# VDMEDA_DisplaySlave.net
KiCad netlist of a schematic drawn in Altium Designer
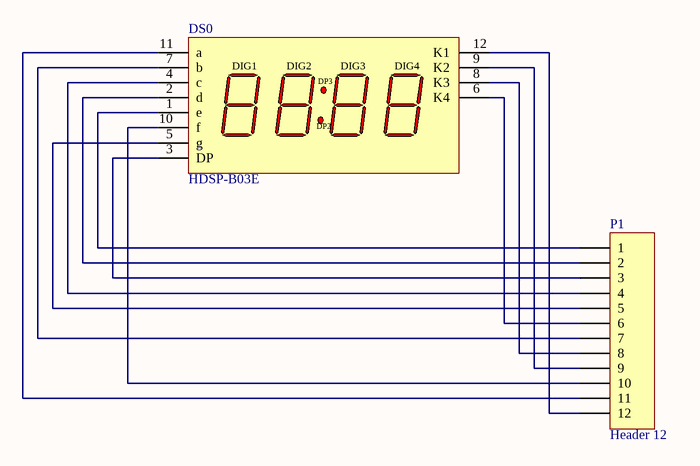
[diagram p0: VDMEDA_DisplaySlave.SchDoc]

(export (version "E")
  (design (tool "Eeschema 10.0.6"))
  (components
    (comp (ref "DS0")
      (value "HDSP-B03E")
      (footprint "B-88")
      (description "14.22 mm GaP HER, Untinted, 88:88 4-Digit 7-Segment Display: CC, Gray Surface")
      (fields (field (name "PUBLISHER") "Altium Limited"))
      (libsource (lib "Agilent LED Display 7-Segment, 4-Digit") (part "HDSP-B03E"))
    )
    (comp (ref "P1")
      (value "Header 12")
      (footprint "HDR1X12")
      (description "Header, 12-Pin")
      (fields (field (name "PUBLISHER") "Altium Limited"))
      (libsource (lib "Miscellaneous Connectors") (part "Header 12"))
    )
  )
  (nets
    (net (code "1") (name "Net-(DS0-DP)") (class "Default")
      (node (ref "DS0") (pin "3") (pinfunction "DP_3") (pintype "passive"))
      (node (ref "P1") (pin "3") (pinfunction "3_3") (pintype "passive"))
    )
    (net (code "2") (name "Net-(DS0-K1)") (class "Default")
      (node (ref "DS0") (pin "12") (pinfunction "K1_12") (pintype "passive"))
      (node (ref "P1") (pin "12") (pinfunction "12_12") (pintype "passive"))
    )
    (net (code "3") (name "Net-(DS0-K2)") (class "Default")
      (node (ref "DS0") (pin "9") (pinfunction "K2_9") (pintype "passive"))
      (node (ref "P1") (pin "9") (pinfunction "9_9") (pintype "passive"))
    )
    (net (code "4") (name "Net-(DS0-K3)") (class "Default")
      (node (ref "DS0") (pin "8") (pinfunction "K3_8") (pintype "passive"))
      (node (ref "P1") (pin "8") (pinfunction "8_8") (pintype "passive"))
    )
    (net (code "5") (name "Net-(DS0-K4)") (class "Default")
      (node (ref "DS0") (pin "6") (pinfunction "K4_6") (pintype "passive"))
      (node (ref "P1") (pin "6") (pinfunction "6_6") (pintype "passive"))
    )
    (net (code "6") (name "Net-(DS0-a)") (class "Default")
      (node (ref "DS0") (pin "11") (pinfunction "a_11") (pintype "passive"))
      (node (ref "P1") (pin "11") (pinfunction "11_11") (pintype "passive"))
    )
    (net (code "7") (name "Net-(DS0-b)") (class "Default")
      (node (ref "DS0") (pin "7") (pinfunction "b_7") (pintype "passive"))
      (node (ref "P1") (pin "7") (pinfunction "7_7") (pintype "passive"))
    )
    (net (code "8") (name "Net-(DS0-c)") (class "Default")
      (node (ref "DS0") (pin "4") (pinfunction "c_4") (pintype "passive"))
      (node (ref "P1") (pin "4") (pinfunction "4_4") (pintype "passive"))
    )
    (net (code "9") (name "Net-(DS0-d)") (class "Default")
      (node (ref "DS0") (pin "2") (pinfunction "d_2") (pintype "passive"))
      (node (ref "P1") (pin "2") (pinfunction "2_2") (pintype "passive"))
    )
    (net (code "10") (name "Net-(DS0-e)") (class "Default")
      (node (ref "DS0") (pin "1") (pinfunction "e_1") (pintype "passive"))
      (node (ref "P1") (pin "1") (pinfunction "1_1") (pintype "passive"))
    )
    (net (code "11") (name "Net-(DS0-f)") (class "Default")
      (node (ref "DS0") (pin "10") (pinfunction "f_10") (pintype "passive"))
      (node (ref "P1") (pin "10") (pinfunction "10_10") (pintype "passive"))
    )
    (net (code "12") (name "Net-(DS0-g)") (class "Default")
      (node (ref "DS0") (pin "5") (pinfunction "g_5") (pintype "passive"))
      (node (ref "P1") (pin "5") (pinfunction "5_5") (pintype "passive"))
    )
  )
)
